# zif_breakout_v20.net
KiCad netlist of a schematic drawn in EAGLE
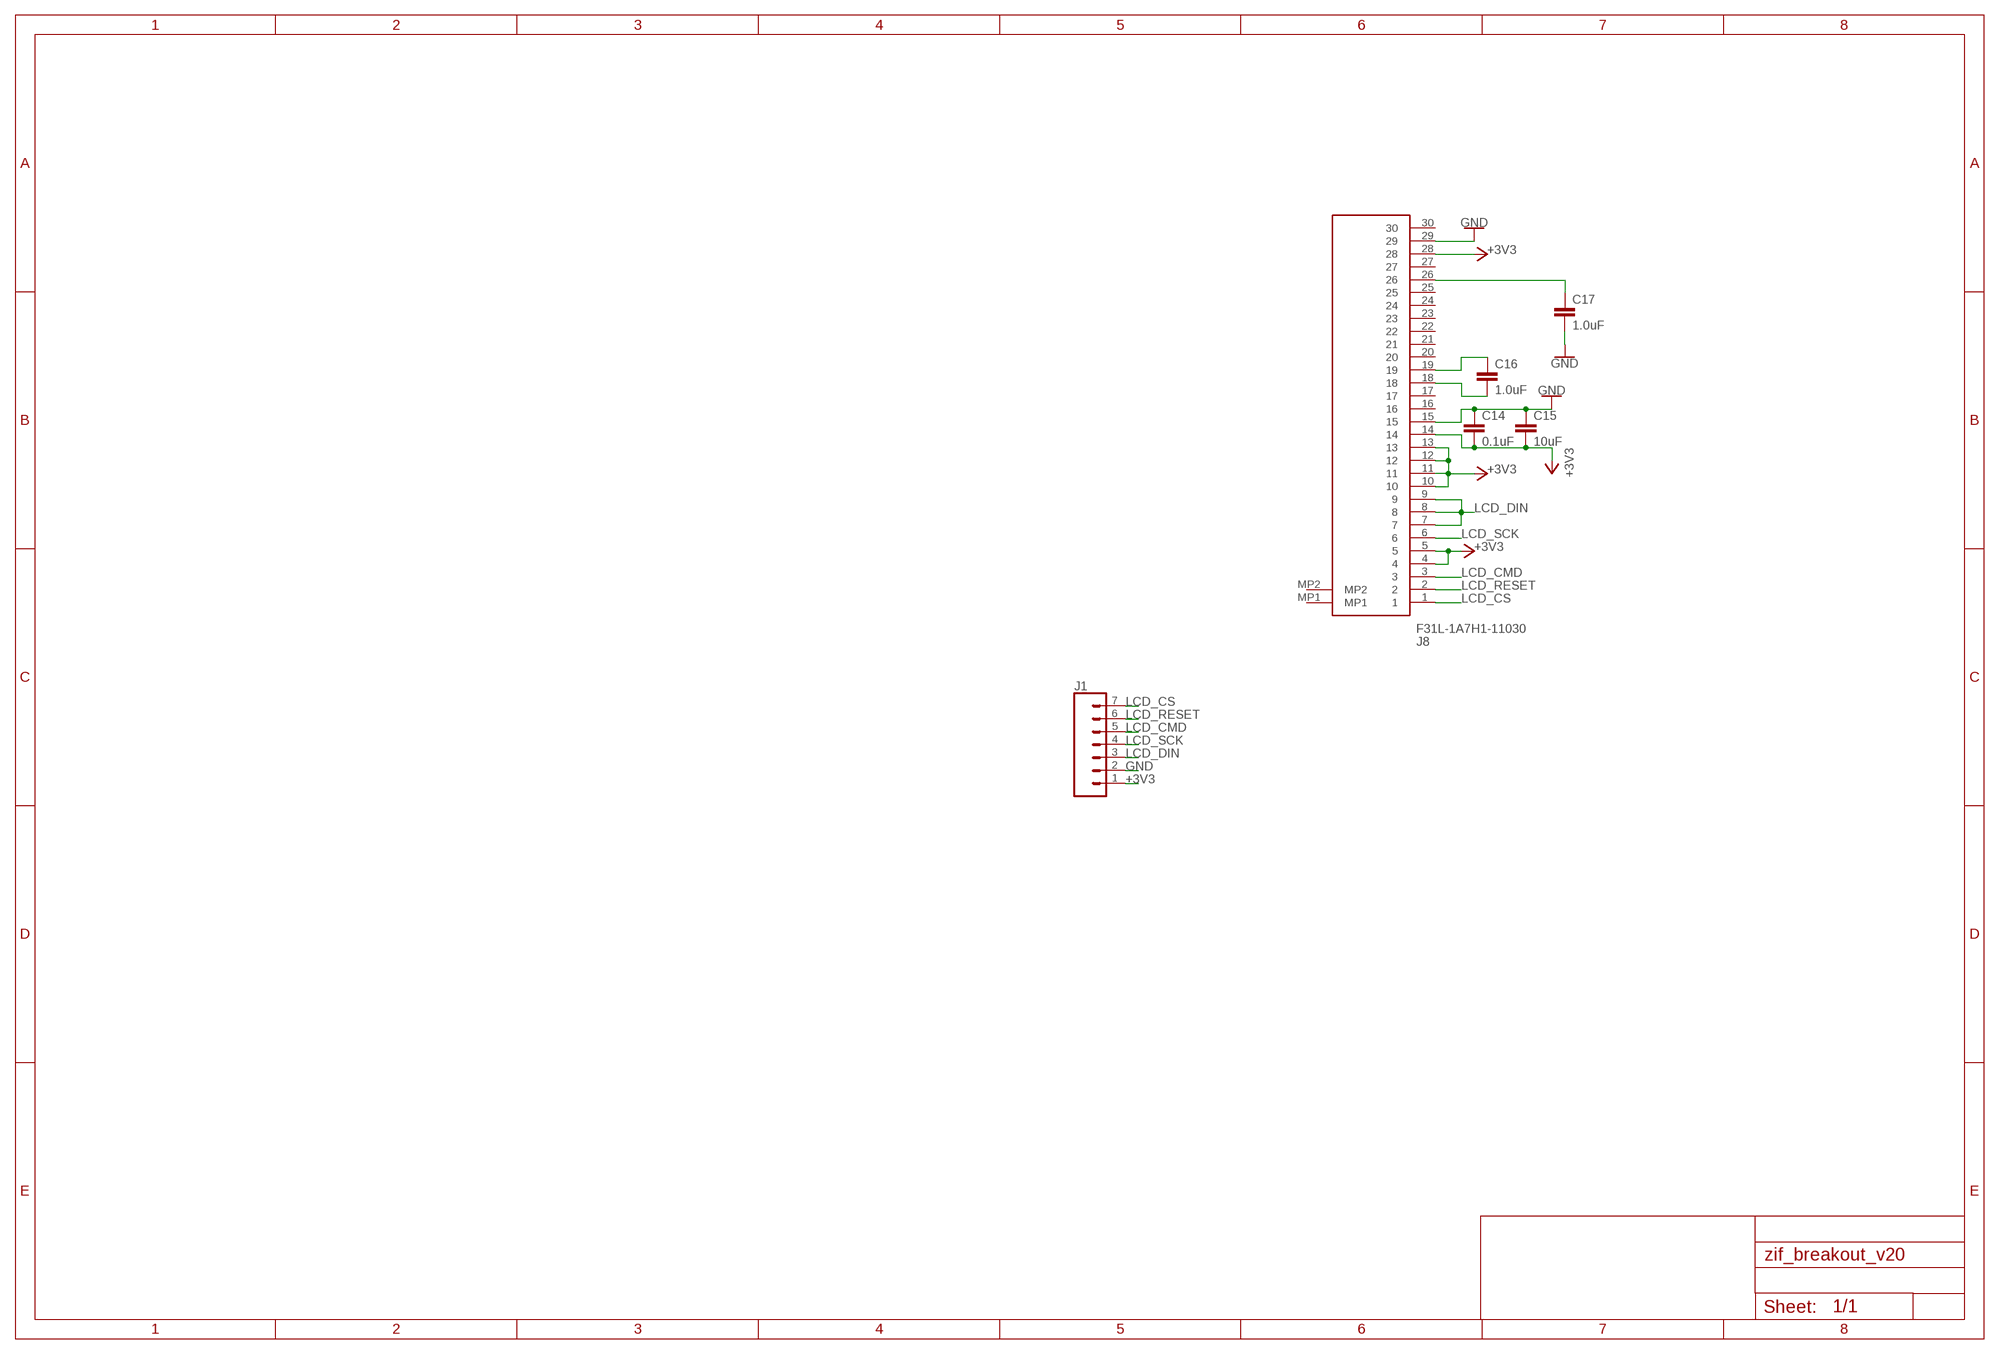
[diagram p0: schematic, sheet 1]

(export (version "E")
  (design (tool "Eeschema 10.0.6"))
  (components
    (comp (ref "C14")
      (value "0.1uF")
      (footprint "eagle-import:0603")
      (libsource (lib "eagle-import") (part "0.1UF-0603-25V-(+80/-20%)"))
    )
    (comp (ref "C15")
      (value "10uF")
      (footprint "eagle-import:0603")
      (libsource (lib "eagle-import") (part "10UF-0603-6.3V-20%"))
    )
    (comp (ref "C16")
      (value "1.0uF")
      (footprint "eagle-import:0603")
      (libsource (lib "eagle-import") (part "1.0UF-0603-16V-10%"))
    )
    (comp (ref "C17")
      (value "1.0uF")
      (footprint "eagle-import:0603")
      (libsource (lib "eagle-import") (part "1.0UF-0603-16V-10%"))
    )
    (comp (ref "J1")
      (value "CONN_07")
      (footprint "eagle-import:1X07")
      (libsource (lib "eagle-import") (part "CONN_07"))
    )
    (comp (ref "J8")
      (value "F31L-1A7H1-11030")
      (footprint "eagle-import:F31L1A7H111030")
      (fields (field (name "MOUSER_PART_NUMBER") "649-F31L-1A7H1-11030"))
      (libsource (lib "eagle-import") (part "F31L-1A7H1-11030"))
    )
  )
  (nets
    (net (code "1") (name "+3V3") (class "Default")
      (node (ref "C14") (pin "2") (pinfunction "2_2") (pintype "passive"))
      (node (ref "C15") (pin "2") (pinfunction "2_2") (pintype "passive"))
      (node (ref "J1") (pin "1") (pinfunction "1_1") (pintype "passive"))
      (node (ref "J8") (pin "10") (pinfunction "10_10") (pintype "bidirectional"))
      (node (ref "J8") (pin "11") (pinfunction "11_11") (pintype "bidirectional"))
      (node (ref "J8") (pin "12") (pinfunction "12_12") (pintype "bidirectional"))
      (node (ref "J8") (pin "13") (pinfunction "13_13") (pintype "bidirectional"))
      (node (ref "J8") (pin "14") (pinfunction "14_14") (pintype "bidirectional"))
      (node (ref "J8") (pin "28") (pinfunction "28_28") (pintype "bidirectional"))
      (node (ref "J8") (pin "4") (pinfunction "4_4") (pintype "bidirectional"))
      (node (ref "J8") (pin "5") (pinfunction "5_5") (pintype "bidirectional"))
    )
    (net (code "2") (name "/LCD_CMD") (class "Default")
      (node (ref "J1") (pin "5") (pinfunction "5_5") (pintype "passive"))
      (node (ref "J8") (pin "3") (pinfunction "3_3") (pintype "bidirectional"))
    )
    (net (code "3") (name "/LCD_CS") (class "Default")
      (node (ref "J1") (pin "7") (pinfunction "7_7") (pintype "passive"))
      (node (ref "J8") (pin "1") (pinfunction "1_1") (pintype "bidirectional"))
    )
    (net (code "4") (name "/LCD_DIN") (class "Default")
      (node (ref "J1") (pin "3") (pinfunction "3_3") (pintype "passive"))
      (node (ref "J8") (pin "7") (pinfunction "7_7") (pintype "bidirectional"))
      (node (ref "J8") (pin "8") (pinfunction "8_8") (pintype "bidirectional"))
      (node (ref "J8") (pin "9") (pinfunction "9_9") (pintype "bidirectional"))
    )
    (net (code "5") (name "/LCD_RESET") (class "Default")
      (node (ref "J1") (pin "6") (pinfunction "6_6") (pintype "passive"))
      (node (ref "J8") (pin "2") (pinfunction "2_2") (pintype "bidirectional"))
    )
    (net (code "6") (name "/LCD_SCK") (class "Default")
      (node (ref "J1") (pin "4") (pinfunction "4_4") (pintype "passive"))
      (node (ref "J8") (pin "6") (pinfunction "6_6") (pintype "bidirectional"))
    )
    (net (code "7") (name "GND") (class "Default")
      (node (ref "C14") (pin "1") (pinfunction "1_1") (pintype "passive"))
      (node (ref "C15") (pin "1") (pinfunction "1_1") (pintype "passive"))
      (node (ref "C17") (pin "2") (pinfunction "2_2") (pintype "passive"))
      (node (ref "J1") (pin "2") (pinfunction "2_2") (pintype "passive"))
      (node (ref "J8") (pin "15") (pinfunction "15_15") (pintype "bidirectional"))
      (node (ref "J8") (pin "29") (pinfunction "29_29") (pintype "bidirectional"))
    )
    (net (code "8") (name "Net-(C16-Pad1)") (class "Default")
      (node (ref "C16") (pin "1") (pinfunction "1_1") (pintype "passive"))
      (node (ref "J8") (pin "19") (pinfunction "19_19") (pintype "bidirectional"))
    )
    (net (code "9") (name "Net-(C16-Pad2)") (class "Default")
      (node (ref "C16") (pin "2") (pinfunction "2_2") (pintype "passive"))
      (node (ref "J8") (pin "18") (pinfunction "18_18") (pintype "bidirectional"))
    )
    (net (code "10") (name "Net-(C17-Pad1)") (class "Default")
      (node (ref "C17") (pin "1") (pinfunction "1_1") (pintype "passive"))
      (node (ref "J8") (pin "26") (pinfunction "26_26") (pintype "bidirectional"))
    )
    (net (code "11") (name "unconnected-(J8-Pad16)") (class "Default")
      (node (ref "J8") (pin "16") (pinfunction "16_16") (pintype "bidirectional"))
    )
    (net (code "12") (name "unconnected-(J8-Pad17)") (class "Default")
      (node (ref "J8") (pin "17") (pinfunction "17_17") (pintype "bidirectional"))
    )
    (net (code "13") (name "unconnected-(J8-Pad20)") (class "Default")
      (node (ref "J8") (pin "20") (pinfunction "20_20") (pintype "bidirectional"))
    )
    (net (code "14") (name "unconnected-(J8-Pad21)") (class "Default")
      (node (ref "J8") (pin "21") (pinfunction "21_21") (pintype "bidirectional"))
    )
    (net (code "15") (name "unconnected-(J8-Pad22)") (class "Default")
      (node (ref "J8") (pin "22") (pinfunction "22_22") (pintype "bidirectional"))
    )
    (net (code "16") (name "unconnected-(J8-Pad23)") (class "Default")
      (node (ref "J8") (pin "23") (pinfunction "23_23") (pintype "bidirectional"))
    )
    (net (code "17") (name "unconnected-(J8-Pad24)") (class "Default")
      (node (ref "J8") (pin "24") (pinfunction "24_24") (pintype "bidirectional"))
    )
    (net (code "18") (name "unconnected-(J8-Pad25)") (class "Default")
      (node (ref "J8") (pin "25") (pinfunction "25_25") (pintype "bidirectional"))
    )
    (net (code "19") (name "unconnected-(J8-Pad27)") (class "Default")
      (node (ref "J8") (pin "27") (pinfunction "27_27") (pintype "bidirectional"))
    )
    (net (code "20") (name "unconnected-(J8-Pad30)") (class "Default")
      (node (ref "J8") (pin "30") (pinfunction "30_30") (pintype "bidirectional"))
    )
    (net (code "21") (name "unconnected-(J8-PadMP1)") (class "Default")
      (node (ref "J8") (pin "MP1") (pinfunction "MP1_MP1") (pintype "bidirectional"))
    )
    (net (code "22") (name "unconnected-(J8-PadMP2)") (class "Default")
      (node (ref "J8") (pin "MP2") (pinfunction "MP2_MP2") (pintype "bidirectional"))
    )
  )
)
